# BB_PowerSuppyandMotorDriver_REV1_0.net
KiCad netlist of a schematic drawn in Altium Designer
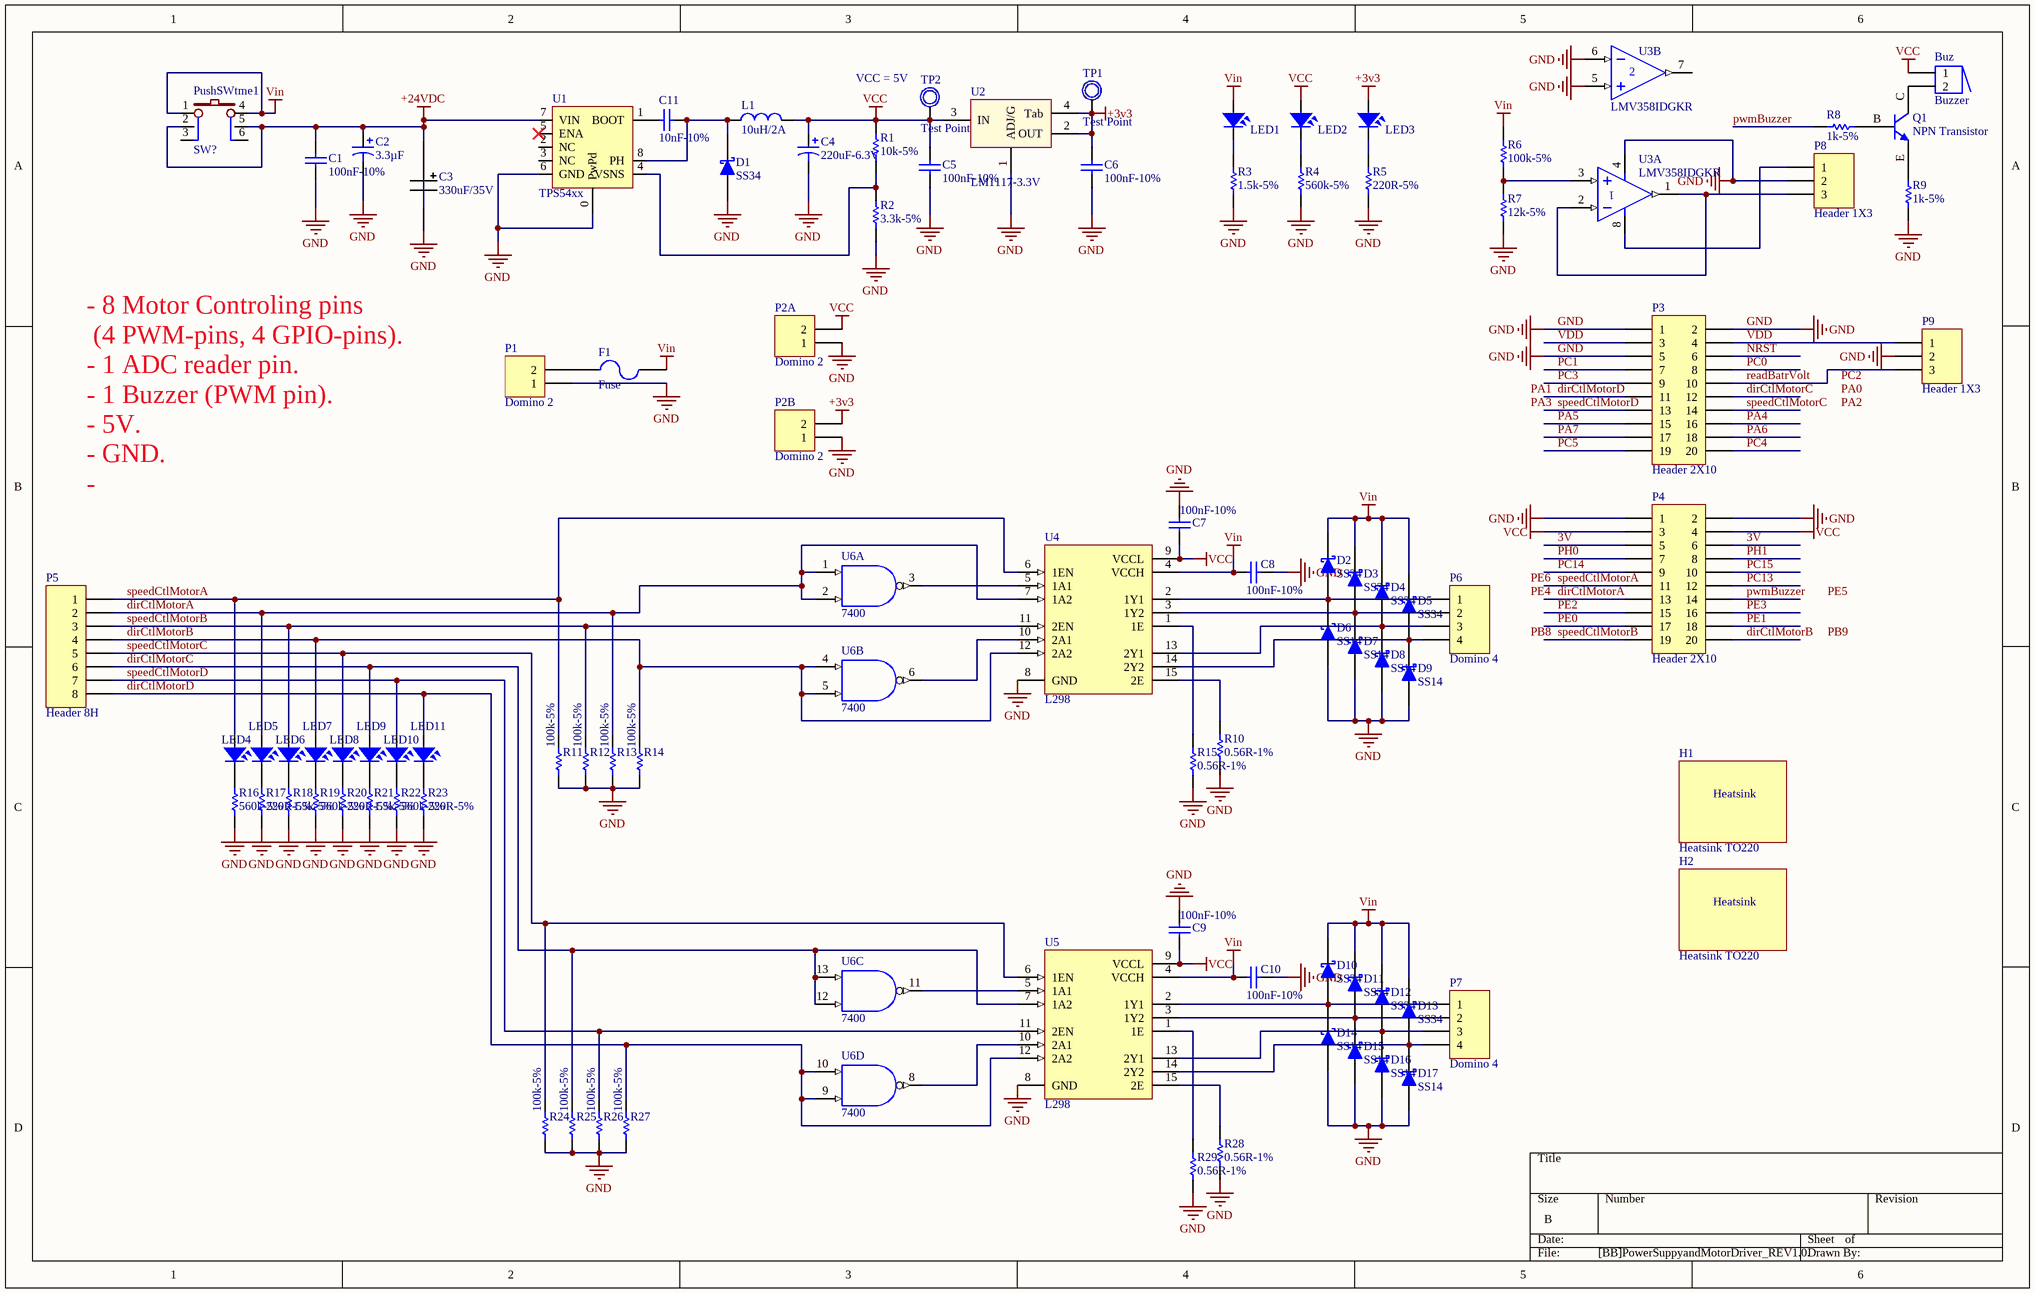
[diagram p0: [BB]PowerSuppyandMotorDriver_REV1.0.SchDoc]

(export (version "E")
  (design (tool "Eeschema 10.0.6"))
  (components
    (comp (ref "Buz")
      (value "Buzzer")
      (footprint "BUZZER SMD")
      (libsource (lib "PIF_Library") (part "Buzzer"))
    )
    (comp (ref "C1")
      (value "100nF-10%")
      (footprint "C0805")
      (description "Non-Polarized Capacitor")
      (fields (field (name "DIGI-KEY PART NUMBER") "311-1140-1-ND") (field (name "MANUFACTURER") "Yageo"))
      (libsource (lib "Capacitor") (part "100nF-50V-C0805"))
    )
    (comp (ref "C2")
      (value "3.3µF")
      (footprint "SM/C_ALU_SA")
      (description "Tantalum Capacitor")
      (fields
        (field (name "MANUFACTURER") "Panasonic Electronic Components")
        (field (name "MANUFACTURER PART NUMBER") "EEE-FC1V3R3R")
      )
      (libsource (lib "Capacitor") (part "4.7uF-25V-Tantalum"))
    )
    (comp (ref "C3")
      (value "330uF/35V")
      (footprint "Size G")
      (description "CAP ALUM 330UF 20% 35V SMD")
      (fields
        (field (name "DIGI-KEY PART NUMBER") "PCE3959CT-ND")
        (field (name "MANUFACTURER") "Panasonic Electronic Components")
      )
      (libsource (lib "Capacitors") (part "C_ALU_330uF_35V"))
    )
    (comp (ref "C4")
      (value "220uF-6.3V")
      (footprint "SM/C_ALU_SD8")
      (description "Tantalum Capacitor")
      (fields
        (field (name "DIGI-KEY PART NUMBER") "478-1713-1-ND")
        (field (name "MANUFACTURER") "AVX Corporation")
      )
      (libsource (lib "Capacitor") (part "220uF-6.3V-Tantalum"))
    )
    (comp (ref "C5")
      (value "100nF-10%")
      (footprint "C0805")
      (description "Non-Polarized Capacitor")
      (fields (field (name "DIGI-KEY PART NUMBER") "311-1140-1-ND") (field (name "MANUFACTURER") "Yageo"))
      (libsource (lib "Capacitor") (part "100nF-50V-C0805"))
    )
    (comp (ref "C6")
      (value "100nF-10%")
      (footprint "C0805")
      (description "Non-Polarized Capacitor")
      (fields (field (name "DIGI-KEY PART NUMBER") "311-1140-1-ND") (field (name "MANUFACTURER") "Yageo"))
      (libsource (lib "Capacitor") (part "100nF-50V-C0805"))
    )
    (comp (ref "C7")
      (value "100nF-10%")
      (footprint "C0805")
      (description "Non-Polarized Capacitor")
      (fields (field (name "DIGI-KEY PART NUMBER") "311-1140-1-ND") (field (name "MANUFACTURER") "Yageo"))
      (libsource (lib "Capacitor") (part "100nF-50V-C0805"))
    )
    (comp (ref "C8")
      (value "100nF-10%")
      (footprint "C0805")
      (description "Non-Polarized Capacitor")
      (fields (field (name "DIGI-KEY PART NUMBER") "311-1140-1-ND") (field (name "MANUFACTURER") "Yageo"))
      (libsource (lib "Capacitor") (part "100nF-50V-C0805"))
    )
    (comp (ref "C9")
      (value "100nF-10%")
      (footprint "C0805")
      (description "Non-Polarized Capacitor")
      (fields (field (name "DIGI-KEY PART NUMBER") "311-1140-1-ND") (field (name "MANUFACTURER") "Yageo"))
      (libsource (lib "Capacitor") (part "100nF-50V-C0805"))
    )
    (comp (ref "C10")
      (value "100nF-10%")
      (footprint "C0805")
      (description "Non-Polarized Capacitor")
      (fields (field (name "DIGI-KEY PART NUMBER") "311-1140-1-ND") (field (name "MANUFACTURER") "Yageo"))
      (libsource (lib "Capacitor") (part "100nF-50V-C0805"))
    )
    (comp (ref "C11")
      (value "10nF-10%")
      (footprint "C0805")
      (description "Non-Polarized Capacitor")
      (fields (field (name "DIGI-KEY PART NUMBER") "311-1136-1-ND") (field (name "MANUFACTURER") "Yageo"))
      (libsource (lib "Capacitor") (part "10nF-50V-C0805"))
    )
    (comp (ref "D1")
      (value "SS34")
      (footprint "DO-214AC (SMA)")
      (description "DIODE SCHOTTKY 40V 1A DO214AC")
      (fields
        (field (name "DIGI-KEY PART NUMBER") "SS14-E3/61TGITR-ND")
        (field (name "MANUFACTURER") "Vishay Semiconductor Diodes Division")
      )
      (libsource (lib "Active Components") (part "Diode_SS14"))
    )
    (comp (ref "D2")
      (value "SS34")
      (footprint "DO-214AC (SMA)")
      (description "DIODE SCHOTTKY 40V 1A DO214AC")
      (fields
        (field (name "DIGI-KEY PART NUMBER") "SS14-E3/61TGITR-ND")
        (field (name "MANUFACTURER") "Vishay Semiconductor Diodes Division")
      )
      (libsource (lib "Active Components") (part "Diode_SS14"))
    )
    (comp (ref "D3")
      (value "SS34")
      (footprint "DO-214AC (SMA)")
      (description "DIODE SCHOTTKY 40V 1A DO214AC")
      (fields
        (field (name "DIGI-KEY PART NUMBER") "SS14-E3/61TGITR-ND")
        (field (name "MANUFACTURER") "Vishay Semiconductor Diodes Division")
      )
      (libsource (lib "Active Components") (part "Diode_SS14"))
    )
    (comp (ref "D4")
      (value "SS34")
      (footprint "DO-214AC (SMA)")
      (description "DIODE SCHOTTKY 40V 1A DO214AC")
      (fields
        (field (name "DIGI-KEY PART NUMBER") "SS14-E3/61TGITR-ND")
        (field (name "MANUFACTURER") "Vishay Semiconductor Diodes Division")
      )
      (libsource (lib "Active Components") (part "Diode_SS14"))
    )
    (comp (ref "D5")
      (value "SS34")
      (footprint "DO-214AC (SMA)")
      (description "DIODE SCHOTTKY 40V 1A DO214AC")
      (fields
        (field (name "DIGI-KEY PART NUMBER") "SS14-E3/61TGITR-ND")
        (field (name "MANUFACTURER") "Vishay Semiconductor Diodes Division")
      )
      (libsource (lib "Active Components") (part "Diode_SS14"))
    )
    (comp (ref "D6")
      (value "SS14")
      (footprint "DO-214AC (SMA)")
      (description "DIODE SCHOTTKY 40V 1A DO214AC")
      (fields
        (field (name "DIGI-KEY PART NUMBER") "SS14-E3/61TGITR-ND")
        (field (name "MANUFACTURER") "Vishay Semiconductor Diodes Division")
      )
      (libsource (lib "Active Components") (part "Diode_SS14"))
    )
    (comp (ref "D7")
      (value "SS14")
      (footprint "DO-214AC (SMA)")
      (description "DIODE SCHOTTKY 40V 1A DO214AC")
      (fields
        (field (name "DIGI-KEY PART NUMBER") "SS14-E3/61TGITR-ND")
        (field (name "MANUFACTURER") "Vishay Semiconductor Diodes Division")
      )
      (libsource (lib "Active Components") (part "Diode_SS14"))
    )
    (comp (ref "D8")
      (value "SS14")
      (footprint "DO-214AC (SMA)")
      (description "DIODE SCHOTTKY 40V 1A DO214AC")
      (fields
        (field (name "DIGI-KEY PART NUMBER") "SS14-E3/61TGITR-ND")
        (field (name "MANUFACTURER") "Vishay Semiconductor Diodes Division")
      )
      (libsource (lib "Active Components") (part "Diode_SS14"))
    )
    (comp (ref "D9")
      (value "SS14")
      (footprint "DO-214AC (SMA)")
      (description "DIODE SCHOTTKY 40V 1A DO214AC")
      (fields
        (field (name "DIGI-KEY PART NUMBER") "SS14-E3/61TGITR-ND")
        (field (name "MANUFACTURER") "Vishay Semiconductor Diodes Division")
      )
      (libsource (lib "Active Components") (part "Diode_SS14"))
    )
    (comp (ref "D10")
      (value "SS34")
      (footprint "DO-214AC (SMA)")
      (description "DIODE SCHOTTKY 40V 1A DO214AC")
      (fields
        (field (name "DIGI-KEY PART NUMBER") "SS14-E3/61TGITR-ND")
        (field (name "MANUFACTURER") "Vishay Semiconductor Diodes Division")
      )
      (libsource (lib "Active Components") (part "Diode_SS14"))
    )
    (comp (ref "D11")
      (value "SS34")
      (footprint "DO-214AC (SMA)")
      (description "DIODE SCHOTTKY 40V 1A DO214AC")
      (fields
        (field (name "DIGI-KEY PART NUMBER") "SS14-E3/61TGITR-ND")
        (field (name "MANUFACTURER") "Vishay Semiconductor Diodes Division")
      )
      (libsource (lib "Active Components") (part "Diode_SS14"))
    )
    (comp (ref "D12")
      (value "SS34")
      (footprint "DO-214AC (SMA)")
      (description "DIODE SCHOTTKY 40V 1A DO214AC")
      (fields
        (field (name "DIGI-KEY PART NUMBER") "SS14-E3/61TGITR-ND")
        (field (name "MANUFACTURER") "Vishay Semiconductor Diodes Division")
      )
      (libsource (lib "Active Components") (part "Diode_SS14"))
    )
    (comp (ref "D13")
      (value "SS34")
      (footprint "DO-214AC (SMA)")
      (description "DIODE SCHOTTKY 40V 1A DO214AC")
      (fields
        (field (name "DIGI-KEY PART NUMBER") "SS14-E3/61TGITR-ND")
        (field (name "MANUFACTURER") "Vishay Semiconductor Diodes Division")
      )
      (libsource (lib "Active Components") (part "Diode_SS14"))
    )
    (comp (ref "D14")
      (value "SS14")
      (footprint "DO-214AC (SMA)")
      (description "DIODE SCHOTTKY 40V 1A DO214AC")
      (fields
        (field (name "DIGI-KEY PART NUMBER") "SS14-E3/61TGITR-ND")
        (field (name "MANUFACTURER") "Vishay Semiconductor Diodes Division")
      )
      (libsource (lib "Active Components") (part "Diode_SS14"))
    )
    (comp (ref "D15")
      (value "SS14")
      (footprint "DO-214AC (SMA)")
      (description "DIODE SCHOTTKY 40V 1A DO214AC")
      (fields
        (field (name "DIGI-KEY PART NUMBER") "SS14-E3/61TGITR-ND")
        (field (name "MANUFACTURER") "Vishay Semiconductor Diodes Division")
      )
      (libsource (lib "Active Components") (part "Diode_SS14"))
    )
    (comp (ref "D16")
      (value "SS14")
      (footprint "DO-214AC (SMA)")
      (description "DIODE SCHOTTKY 40V 1A DO214AC")
      (fields
        (field (name "DIGI-KEY PART NUMBER") "SS14-E3/61TGITR-ND")
        (field (name "MANUFACTURER") "Vishay Semiconductor Diodes Division")
      )
      (libsource (lib "Active Components") (part "Diode_SS14"))
    )
    (comp (ref "D17")
      (value "SS14")
      (footprint "DO-214AC (SMA)")
      (description "DIODE SCHOTTKY 40V 1A DO214AC")
      (fields
        (field (name "DIGI-KEY PART NUMBER") "SS14-E3/61TGITR-ND")
        (field (name "MANUFACTURER") "Vishay Semiconductor Diodes Division")
      )
      (libsource (lib "Active Components") (part "Diode_SS14"))
    )
    (comp (ref "F1")
      (value "Fuse")
      (footprint "FUSE")
      (fields (field (name "PUBLISHER") "Altium Limited"))
      (libsource (lib "Others") (part "Fuse"))
    )
    (comp (ref "H1")
      (value "Heatsink TO220")
      (footprint "Heatsink TO-220")
      (description "Heatsink-231625W Tản nhiệt Nhôm kiểu TO-220 / Multiwatt, 23x16x25mm")
      (libsource (lib "Heatsink") (part "Heatsink TO220"))
    )
    (comp (ref "H2")
      (value "Heatsink TO220")
      (footprint "Heatsink TO-220")
      (description "Heatsink-231625W Tản nhiệt Nhôm kiểu TO-220 / Multiwatt, 23x16x25mm")
      (libsource (lib "Heatsink") (part "Heatsink TO220"))
    )
    (comp (ref "L1")
      (value "10uH/2A")
      (footprint "L6D38")
      (description "10uH/2A ±20% SMD 6.7x6.7x4mm Inductor")
      (libsource (lib "Inductor") (part "L6D38-100M"))
    )
    (comp (ref "LED1")
      (value "LED SMD")
      (footprint "SM-LED-0805-Blue")
      (libsource (lib "syhaunguyen") (part "LED-SMD-0805"))
    )
    (comp (ref "LED2")
      (value "LED SMD")
      (footprint "SM-LED-0805-Blue")
      (libsource (lib "syhaunguyen") (part "LED-SMD-0805"))
    )
    (comp (ref "LED3")
      (value "LED SMD")
      (footprint "SM-LED-0805-Blue")
      (libsource (lib "syhaunguyen") (part "LED-SMD-0805"))
    )
    (comp (ref "LED4")
      (value "LED SMD")
      (footprint "SM-LED-0805-Blue")
      (libsource (lib "syhaunguyen") (part "LED-SMD-0805"))
    )
    (comp (ref "LED5")
      (value "LED SMD")
      (footprint "SM-LED-0805-Blue")
      (libsource (lib "syhaunguyen") (part "LED-SMD-0805"))
    )
    (comp (ref "LED6")
      (value "LED SMD")
      (footprint "SM-LED-0805-Blue")
      (libsource (lib "syhaunguyen") (part "LED-SMD-0805"))
    )
    (comp (ref "LED7")
      (value "LED SMD")
      (footprint "SM-LED-0805-Blue")
      (libsource (lib "syhaunguyen") (part "LED-SMD-0805"))
    )
    (comp (ref "LED8")
      (value "LED SMD")
      (footprint "SM-LED-0805-Blue")
      (libsource (lib "syhaunguyen") (part "LED-SMD-0805"))
    )
    (comp (ref "LED9")
      (value "LED SMD")
      (footprint "SM-LED-0805-Blue")
      (libsource (lib "syhaunguyen") (part "LED-SMD-0805"))
    )
    (comp (ref "LED10")
      (value "LED SMD")
      (footprint "SM-LED-0805-Blue")
      (libsource (lib "syhaunguyen") (part "LED-SMD-0805"))
    )
    (comp (ref "LED11")
      (value "LED SMD")
      (footprint "SM-LED-0805-Blue")
      (libsource (lib "syhaunguyen") (part "LED-SMD-0805"))
    )
    (comp (ref "P1")
      (value "Domino 2")
      (footprint "DOMINO 2- 5mm")
      (description "Domino, 2-Pin")
      (fields (field (name "PUBLISHER") "Altium Limited"))
      (libsource (lib "PIF_Library") (part "Domino 2"))
    )
    (comp (ref "P2A")
      (value "Domino 2")
      (footprint "DOMINO 2- 5mm")
      (description "Domino, 2-Pin")
      (fields (field (name "PUBLISHER") "Altium Limited"))
      (libsource (lib "PIF_Library") (part "Domino 2"))
    )
    (comp (ref "P2B")
      (value "Domino 2")
      (footprint "DOMINO 2- 5mm")
      (description "Domino, 2-Pin")
      (fields (field (name "PUBLISHER") "Altium Limited"))
      (libsource (lib "PIF_Library") (part "Domino 2"))
    )
    (comp (ref "P3")
      (value "Header 2X10")
      (footprint "Header 2X10")
      (description "Header, 10-Pin, Dual row")
      (libsource (lib "Connector") (part "Header 2X10"))
    )
    (comp (ref "P4")
      (value "Header 2X10")
      (footprint "Header 2X10")
      (description "Header, 10-Pin, Dual row")
      (libsource (lib "Connector") (part "Header 2X10"))
    )
    (comp (ref "P5")
      (value "Header 8H")
      (footprint "JP8H")
      (description "Header, 8-Pin, Right Angle")
      (fields (field (name "PUBLISHER") "Altium Limited"))
      (libsource (lib "PIF_Library") (part "Header 8H"))
    )
    (comp (ref "P6")
      (value "Domino 4")
      (footprint "DOMINO 4 -5mm")
      (description "Domino 4-Pin")
      (fields (field (name "PUBLISHER") "Altium Limited"))
      (libsource (lib "PIF_Library") (part "Domino 4"))
    )
    (comp (ref "P7")
      (value "Domino 4")
      (footprint "DOMINO 4 -5mm")
      (description "Domino 4-Pin")
      (fields (field (name "PUBLISHER") "Altium Limited"))
      (libsource (lib "PIF_Library") (part "Domino 4"))
    )
    (comp (ref "P8")
      (value "Header 1X3")
      (footprint "Header 1X3")
      (description "Header, 3-Pin")
      (libsource (lib "Connector") (part "Header 1X3"))
    )
    (comp (ref "P9")
      (value "Header 1X3")
      (footprint "Header 1X3")
      (description "Header, 3-Pin")
      (libsource (lib "Connector") (part "Header 1X3"))
    )
    (comp (ref "PushSWtme1")
      (value "SW?")
      (footprint "PUSH SW")
      (description "Push SW 8x8 mm latching ON/OFF")
      (libsource (lib "Switch, Button & Relay") (part "PushSWtme"))
    )
    (comp (ref "Q1")
      (value "NPN Transistor")
      (footprint "SC-43-BCE")
      (libsource (lib "Transistor") (part "NPN Transistor"))
    )
    (comp (ref "R1")
      (value "10k-5%")
      (footprint "R0805")
      (description "RES 10k OHM 1/8W 5% 0805 SMD")
      (fields (field (name "DIGI-KEY PART NUMBER") "311-10KARTR-ND") (field (name "MANUFACTURER") "Yageo"))
      (libsource (lib "Resistor") (part "10k-5%-R0805"))
    )
    (comp (ref "R2")
      (value "3.3k-5%")
      (footprint "R0805")
      (description "RES 3.3k OHM 1/8W 5% 0805 SMD")
      (fields (field (name "DIGI-KEY PART NUMBER") "311-3.3KARTR-ND") (field (name "MANUFACTURER") "Yageo"))
      (libsource (lib "Resistor") (part "3.3k-5%-R0805"))
    )
    (comp (ref "R3")
      (value "1.5k-5%")
      (footprint "R0805")
      (description "RES 1.5k OHM 1/8W 5% 0805 SMD")
      (fields (field (name "DIGI-KEY PART NUMBER") "311-1.5KARTR-ND") (field (name "MANUFACTURER") "Yageo"))
      (libsource (lib "Resistor") (part "1.5k-5%-R0805"))
    )
    (comp (ref "R4")
      (value "560k-5%")
      (footprint "R0805")
      (description "RES 560k OHM 1/10W 5% 0603 SMD")
      (fields (field (name "DIGI-KEY PART NUMBER") "311-560KGRTR-ND") (field (name "MANUFACTURER") "Yageo"))
      (libsource (lib "Resistor") (part "560k-5%-R0603"))
    )
    (comp (ref "R5")
      (value "220R-5%")
      (footprint "R0805")
      (description "RES 220 OHM 1/8W 5% 0805 SMD")
      (fields (field (name "DIGI-KEY PART NUMBER") "311-220ARTR-ND") (field (name "MANUFACTURER") "Yageo"))
      (libsource (lib "Resistor") (part "220R-5%-R0805"))
    )
    (comp (ref "R6")
      (value "100k-5%")
      (footprint "R0805")
      (description "RES 100k OHM 1/8W 5% 0805 SMD")
      (fields (field (name "DIGI-KEY PART NUMBER") "311-100KARTR-ND") (field (name "MANUFACTURER") "Yageo"))
      (libsource (lib "Resistor") (part "100k-5%-R0805"))
    )
    (comp (ref "R7")
      (value "12k-5%")
      (footprint "R0805")
      (description "RES 12k OHM 1/8W 5% 0805 SMD")
      (fields (field (name "DIGI-KEY PART NUMBER") "311-12KARTR-ND") (field (name "MANUFACTURER") "Yageo"))
      (libsource (lib "Resistor") (part "12k-5%-R0805"))
    )
    (comp (ref "R8")
      (value "1k-5%")
      (footprint "R0805")
      (description "RES 1k OHM 1/8W 5% 0805 SMD")
      (fields (field (name "DIGI-KEY PART NUMBER") "311-1.0KARTR-ND") (field (name "MANUFACTURER") "Yageo"))
      (libsource (lib "Resistor") (part "1k-5%-R0805"))
    )
    (comp (ref "R9")
      (value "1k-5%")
      (footprint "R0805")
      (description "RES 1k OHM 1/8W 5% 0805 SMD")
      (fields (field (name "DIGI-KEY PART NUMBER") "311-1.0KARTR-ND") (field (name "MANUFACTURER") "Yageo"))
      (libsource (lib "Resistor") (part "1k-5%-R0805"))
    )
    (comp (ref "R10")
      (value "0.56R-1%")
      (footprint "R0805")
      (description "RES 0.56 OHM 1/10W 1% 0603 SMD")
      (fields (field (name "DIGI-KEY PART NUMBER") "311-.56QTR-ND") (field (name "MANUFACTURER") "Yageo"))
      (libsource (lib "Resistor") (part "0.56R-1%-R0603"))
    )
    (comp (ref "R11")
      (value "100k-5%")
      (footprint "R0805")
      (description "RES 100k OHM 1/8W 5% 0805 SMD")
      (fields (field (name "DIGI-KEY PART NUMBER") "311-100KARTR-ND") (field (name "MANUFACTURER") "Yageo"))
      (libsource (lib "Resistor") (part "100k-5%-R0805"))
    )
    (comp (ref "R12")
      (value "100k-5%")
      (footprint "R0805")
      (description "RES 100k OHM 1/8W 5% 0805 SMD")
      (fields (field (name "DIGI-KEY PART NUMBER") "311-100KARTR-ND") (field (name "MANUFACTURER") "Yageo"))
      (libsource (lib "Resistor") (part "100k-5%-R0805"))
    )
    (comp (ref "R13")
      (value "100k-5%")
      (footprint "R0805")
      (description "RES 100k OHM 1/8W 5% 0805 SMD")
      (fields (field (name "DIGI-KEY PART NUMBER") "311-100KARTR-ND") (field (name "MANUFACTURER") "Yageo"))
      (libsource (lib "Resistor") (part "100k-5%-R0805"))
    )
    (comp (ref "R14")
      (value "100k-5%")
      (footprint "R0805")
      (description "RES 100k OHM 1/8W 5% 0805 SMD")
      (fields (field (name "DIGI-KEY PART NUMBER") "311-100KARTR-ND") (field (name "MANUFACTURER") "Yageo"))
      (libsource (lib "Resistor") (part "100k-5%-R0805"))
    )
    (comp (ref "R15")
      (value "0.56R-1%")
      (footprint "R0805")
      (description "RES 0.56 OHM 1/10W 1% 0603 SMD")
      (fields (field (name "DIGI-KEY PART NUMBER") "311-.56QTR-ND") (field (name "MANUFACTURER") "Yageo"))
      (libsource (lib "Resistor") (part "0.56R-1%-R0603"))
    )
    (comp (ref "R16")
      (value "560k-5%")
      (footprint "R0805")
      (description "RES 560k OHM 1/10W 5% 0603 SMD")
      (fields (field (name "DIGI-KEY PART NUMBER") "311-560KGRTR-ND") (field (name "MANUFACTURER") "Yageo"))
      (libsource (lib "Resistor") (part "560k-5%-R0603"))
    )
    (comp (ref "R17")
      (value "220R-5%")
      (footprint "R0805")
      (description "RES 220 OHM 1/8W 5% 0805 SMD")
      (fields (field (name "DIGI-KEY PART NUMBER") "311-220ARTR-ND") (field (name "MANUFACTURER") "Yageo"))
      (libsource (lib "Resistor") (part "220R-5%-R0805"))
    )
    (comp (ref "R18")
      (value "1.5k-5%")
      (footprint "R0805")
      (description "RES 1.5k OHM 1/8W 5% 0805 SMD")
      (fields (field (name "DIGI-KEY PART NUMBER") "311-1.5KARTR-ND") (field (name "MANUFACTURER") "Yageo"))
      (libsource (lib "Resistor") (part "1.5k-5%-R0805"))
    )
    (comp (ref "R19")
      (value "560k-5%")
      (footprint "R0805")
      (description "RES 560k OHM 1/10W 5% 0603 SMD")
      (fields (field (name "DIGI-KEY PART NUMBER") "311-560KGRTR-ND") (field (name "MANUFACTURER") "Yageo"))
      (libsource (lib "Resistor") (part "560k-5%-R0603"))
    )
    (comp (ref "R20")
      (value "220R-5%")
      (footprint "R0805")
      (description "RES 220 OHM 1/8W 5% 0805 SMD")
      (fields (field (name "DIGI-KEY PART NUMBER") "311-220ARTR-ND") (field (name "MANUFACTURER") "Yageo"))
      (libsource (lib "Resistor") (part "220R-5%-R0805"))
    )
    (comp (ref "R21")
      (value "1.5k-5%")
      (footprint "R0805")
      (description "RES 1.5k OHM 1/8W 5% 0805 SMD")
      (fields (field (name "DIGI-KEY PART NUMBER") "311-1.5KARTR-ND") (field (name "MANUFACTURER") "Yageo"))
      (libsource (lib "Resistor") (part "1.5k-5%-R0805"))
    )
    (comp (ref "R22")
      (value "560k-5%")
      (footprint "R0805")
      (description "RES 560k OHM 1/10W 5% 0603 SMD")
      (fields (field (name "DIGI-KEY PART NUMBER") "311-560KGRTR-ND") (field (name "MANUFACTURER") "Yageo"))
      (libsource (lib "Resistor") (part "560k-5%-R0603"))
    )
    (comp (ref "R23")
      (value "220R-5%")
      (footprint "R0805")
      (description "RES 220 OHM 1/8W 5% 0805 SMD")
      (fields (field (name "DIGI-KEY PART NUMBER") "311-220ARTR-ND") (field (name "MANUFACTURER") "Yageo"))
      (libsource (lib "Resistor") (part "220R-5%-R0805"))
    )
    (comp (ref "R24")
      (value "100k-5%")
      (footprint "R0805")
      (description "RES 100k OHM 1/8W 5% 0805 SMD")
      (fields (field (name "DIGI-KEY PART NUMBER") "311-100KARTR-ND") (field (name "MANUFACTURER") "Yageo"))
      (libsource (lib "Resistor") (part "100k-5%-R0805"))
    )
    (comp (ref "R25")
      (value "100k-5%")
      (footprint "R0805")
      (description "RES 100k OHM 1/8W 5% 0805 SMD")
      (fields (field (name "DIGI-KEY PART NUMBER") "311-100KARTR-ND") (field (name "MANUFACTURER") "Yageo"))
      (libsource (lib "Resistor") (part "100k-5%-R0805"))
    )
    (comp (ref "R26")
      (value "100k-5%")
      (footprint "R0805")
      (description "RES 100k OHM 1/8W 5% 0805 SMD")
      (fields (field (name "DIGI-KEY PART NUMBER") "311-100KARTR-ND") (field (name "MANUFACTURER") "Yageo"))
      (libsource (lib "Resistor") (part "100k-5%-R0805"))
    )
    (comp (ref "R27")
      (value "100k-5%")
      (footprint "R0805")
      (description "RES 100k OHM 1/8W 5% 0805 SMD")
      (fields (field (name "DIGI-KEY PART NUMBER") "311-100KARTR-ND") (field (name "MANUFACTURER") "Yageo"))
      (libsource (lib "Resistor") (part "100k-5%-R0805"))
    )
    (comp (ref "R28")
      (value "0.56R-1%")
      (footprint "R0805")
      (description "RES 0.56 OHM 1/10W 1% 0603 SMD")
      (fields (field (name "DIGI-KEY PART NUMBER") "311-.56QTR-ND") (field (name "MANUFACTURER") "Yageo"))
      (libsource (lib "Resistor") (part "0.56R-1%-R0603"))
    )
    (comp (ref "R29")
      (value "0.56R-1%")
      (footprint "R0805")
      (description "RES 0.56 OHM 1/10W 1% 0603 SMD")
      (fields (field (name "DIGI-KEY PART NUMBER") "311-.56QTR-ND") (field (name "MANUFACTURER") "Yageo"))
      (libsource (lib "Resistor") (part "0.56R-1%-R0603"))
    )
    (comp (ref "TP1")
      (value "Test Point")
      (footprint "Hole 1.5mm")
      (libsource (lib "Connector") (part "Test Point"))
    )
    (comp (ref "TP2")
      (value "Test Point")
      (footprint "Hole 1.5mm")
      (libsource (lib "Connector") (part "Test Point"))
    )
    (comp (ref "U1")
      (value "TPS54xx")
      (footprint "SOIC-8 POWERPAD")
      (description "IC REG BUCK ADJ 1A 8SOIC")
      (fields
        (field (name "DIGI-KEY PART NUMBER") "296-26982-2-ND")
        (field (name "MANUFACTURER") "Texas Instruments")
      )
      (libsource (lib "power_ic") (part "TPS54xx"))
    )
    (comp (ref "U2")
      (value "LM1117-3.3V")
      (footprint "SOT223-4N")
      (description "800mA Low-Dropout Linear Regulator")
      (fields
        (field (name "DIGI-KEY PART NUMBER") "LM1117MPX-3.3/NOPBTR-ND")
        (field (name "MANUFACTURER") "Texas Instruments")
      )
      (libsource (lib "IC") (part "LM1117-3.3V"))
    )
    (comp (ref "U3")
      (value "LMV358IDGKR")
      (footprint "MSOP-8")
      (fields (field (name "MANUFACTURER") "Texas Instruments"))
      (libsource (lib "Opamp-SMD") (part "LMV358IDGKR"))
    )
    (comp (ref "U4")
      (value "L298")
      (footprint "DIP15SL2")
      (description "Dual Full-H Driver")
      (fields (field (name "PUBLISHER") "Altium Limited"))
      (libsource (lib "IC") (part "L298"))
    )
    (comp (ref "U5")
      (value "L298")
      (footprint "DIP15SL2")
      (description "Dual Full-H Driver")
      (fields (field (name "PUBLISHER") "Altium Limited"))
      (libsource (lib "IC") (part "L298"))
    )
    (comp (ref "U6")
      (value "7400")
      (footprint "SO14-150mil")
      (description "Quad 2-Input NAND Gate")
      (libsource (lib "IC") (part "7400"))
    )
  )
  (nets
    (net (code "1") (name "+3v3") (class "Default")
      (node (ref "C6") (pin "2") (pinfunction "2_2") (pintype "passive"))
      (node (ref "LED3") (pin "1") (pinfunction "1_1") (pintype "passive"))
      (node (ref "P2B") (pin "2") (pinfunction "2_2") (pintype "passive"))
      (node (ref "TP1") (pin "0") (pinfunction "0_0") (pintype "passive"))
      (node (ref "U2") (pin "2") (pinfunction "OUT_2") (pintype "passive"))
      (node (ref "U2") (pin "4") (pinfunction "Tab_4") (pintype "passive"))
    )
    (net (code "2") (name "+24VDC") (class "Default")
      (node (ref "C1") (pin "2") (pinfunction "2_2") (pintype "passive"))
      (node (ref "C2") (pin "1") (pinfunction "1_1") (pintype "passive"))
      (node (ref "C3") (pin "1") (pintype "passive"))
      (node (ref "PushSWtme1") (pin "2") (pinfunction "2_2") (pintype "passive"))
      (node (ref "PushSWtme1") (pin "5") (pinfunction "5_5") (pintype "passive"))
      (node (ref "U1") (pin "7") (pinfunction "VIN_7") (pintype "passive"))
    )
    (net (code "3") (name "/3V") (class "Default")
      (node (ref "P4") (pin "5") (pinfunction "5_5") (pintype "passive"))
      (node (ref "P4") (pin "6") (pinfunction "6_6") (pintype "passive"))
    )
    (net (code "4") (name "/NRST") (class "Default")
      (node (ref "P3") (pin "6") (pinfunction "6_6") (pintype "passive"))
    )
    (net (code "9") (name "/PA4") (class "Default")
      (node (ref "P3") (pin "16") (pinfunction "16_16") (pintype "passive"))
    )
    (net (code "10") (name "/PA5") (class "Default")
      (node (ref "P3") (pin "15") (pinfunction "15_15") (pintype "passive"))
    )
    (net (code "11") (name "/PA6") (class "Default")
      (node (ref "P3") (pin "18") (pinfunction "18_18") (pintype "passive"))
    )
    (net (code "12") (name "/PA7") (class "Default")
      (node (ref "P3") (pin "17") (pinfunction "17_17") (pintype "passive"))
    )
    (net (code "15") (name "/PC0") (class "Default")
      (node (ref "P3") (pin "8") (pinfunction "8_8") (pintype "passive"))
    )
    (net (code "16") (name "/PC1") (class "Default")
      (node (ref "P3") (pin "7") (pinfunction "7_7") (pintype "passive"))
    )
    (net (code "18") (name "/PC3") (class "Default")
      (node (ref "P3") (pin "9") (pinfunction "9_9") (pintype "passive"))
    )
    (net (code "19") (name "/PC4") (class "Default")
      (node (ref "P3") (pin "20") (pinfunction "20_20") (pintype "passive"))
    )
    (net (code "20") (name "/PC5") (class "Default")
      (node (ref "P3") (pin "19") (pinfunction "19_19") (pintype "passive"))
    )
    (net (code "21") (name "/PC13") (class "Default")
      (node (ref "P4") (pin "12") (pinfunction "12_12") (pintype "passive"))
    )
    (net (code "22") (name "/PC14") (class "Default")
      (node (ref "P4") (pin "9") (pinfunction "9_9") (pintype "passive"))
    )
    (net (code "23") (name "/PC15") (class "Default")
      (node (ref "P4") (pin "10") (pinfunction "10_10") (pintype "passive"))
    )
    (net (code "24") (name "/PE0") (class "Default")
      (node (ref "P4") (pin "17") (pinfunction "17_17") (pintype "passive"))
    )
    (net (code "25") (name "/PE1") (class "Default")
      (node (ref "P4") (pin "18") (pinfunction "18_18") (pintype "passive"))
    )
    (net (code "26") (name "/PE2") (class "Default")
      (node (ref "P4") (pin "15") (pinfunction "15_15") (pintype "passive"))
    )
    (net (code "27") (name "/PE3") (class "Default")
      (node (ref "P4") (pin "16") (pinfunction "16_16") (pintype "passive"))
    )
    (net (code "31") (name "/PH0") (class "Default")
      (node (ref "P4") (pin "7") (pinfunction "7_7") (pintype "passive"))
    )
    (net (code "32") (name "/PH1") (class "Default")
      (node (ref "P4") (pin "8") (pinfunction "8_8") (pintype "passive"))
    )
    (net (code "33") (name "/VDD") (class "Default")
      (node (ref "P3") (pin "3") (pinfunction "3_3") (pintype "passive"))
      (node (ref "P3") (pin "4") (pinfunction "4_4") (pintype "passive"))
      (node (ref "P9") (pin "1") (pinfunction "1_1") (pintype "passive"))
    )
    (net (code "34") (name "/dirCtlMotorA") (class "Default")
      (node (ref "LED5") (pin "1") (pinfunction "1_1") (pintype "passive"))
      (node (ref "P4") (pin "13") (pinfunction "13_13") (pintype "passive"))
      (node (ref "P5") (pin "2") (pinfunction "2_2") (pintype "passive"))
      (node (ref "R13") (pin "2") (pinfunction "2_2") (pintype "passive"))
      (node (ref "U4") (pin "7") (pinfunction "1A2_7") (pintype "input"))
      (node (ref "U6") (pin "1") (pinfunction "A_1") (pintype "input"))
      (node (ref "U6") (pin "2") (pinfunction "B_2") (pintype "input"))
    )
    (net (code "35") (name "/dirCtlMotorB") (class "Default")
      (node (ref "LED7") (pin "1") (pinfunction "1_1") (pintype "passive"))
      (node (ref "P4") (pin "20") (pinfunction "20_20") (pintype "passive"))
      (node (ref "P5") (pin "4") (pinfunction "4_4") (pintype "passive"))
      (node (ref "R14") (pin "2") (pinfunction "2_2") (pintype "passive"))
      (node (ref "U4") (pin "12") (pinfunction "2A2_12") (pintype "input"))
      (node (ref "U6") (pin "4") (pinfunction "A_4") (pintype "input"))
      (node (ref "U6") (pin "5") (pinfunction "B_5") (pintype "input"))
    )
    (net (code "36") (name "/dirCtlMotorC") (class "Default")
      (node (ref "LED9") (pin "1") (pinfunction "1_1") (pintype "passive"))
      (node (ref "P3") (pin "12") (pinfunction "12_12") (pintype "passive"))
      (node (ref "P5") (pin "6") (pinfunction "6_6") (pintype "passive"))
      (node (ref "R25") (pin "2") (pinfunction "2_2") (pintype "passive"))
      (node (ref "U5") (pin "7") (pinfunction "1A2_7") (pintype "input"))
      (node (ref "U6") (pin "12") (pinfunction "B_12") (pintype "input"))
      (node (ref "U6") (pin "13") (pinfunction "A_13") (pintype "input"))
    )
    (net (code "37") (name "/dirCtlMotorD") (class "Default")
      (node (ref "LED11") (pin "1") (pinfunction "1_1") (pintype "passive"))
      (node (ref "P3") (pin "11") (pinfunction "11_11") (pintype "passive"))
      (node (ref "P5") (pin "8") (pinfunction "8_8") (pintype "passive"))
      (node (ref "R27") (pin "2") (pinfunction "2_2") (pintype "passive"))
      (node (ref "U5") (pin "12") (pinfunction "2A2_12") (pintype "input"))
      (node (ref "U6") (pin "10") (pinfunction "A_10") (pintype "input"))
      (node (ref "U6") (pin "9") (pinfunction "B_9") (pintype "input"))
    )
    (net (code "38") (name "/pwmBuzzer") (class "Default")
      (node (ref "P4") (pin "14") (pinfunction "14_14") (pintype "passive"))
      (node (ref "R8") (pin "1") (pinfunction "1_1") (pintype "passive"))
    )
    (net (code "39") (name "/readBatrVolt") (class "Default")
      (node (ref "P3") (pin "10") (pinfunction "10_10") (pintype "passive"))
      (node (ref "P9") (pin "3") (pinfunction "3_3") (pintype "passive"))
    )
    (net (code "40") (name "/speedCtlMotorA") (class "Default")
      (node (ref "LED4") (pin "1") (pinfunction "1_1") (pintype "passive"))
      (node (ref "P4") (pin "11") (pinfunction "11_11") (pintype "passive"))
      (node (ref "P5") (pin "1") (pinfunction "1_1") (pintype "passive"))
      (node (ref "R11") (pin "2") (pinfunction "2_2") (pintype "passive"))
      (node (ref "U4") (pin "6") (pinfunction "1EN_6") (pintype "input"))
    )
    (net (code "41") (name "/speedCtlMotorB") (class "Default")
      (node (ref "LED6") (pin "1") (pinfunction "1_1") (pintype "passive"))
      (node (ref "P4") (pin "19") (pinfunction "19_19") (pintype "passive"))
      (node (ref "P5") (pin "3") (pinfunction "3_3") (pintype "passive"))
      (node (ref "R12") (pin "2") (pinfunction "2_2") (pintype "passive"))
      (node (ref "U4") (pin "11") (pinfunction "2EN_11") (pintype "input"))
    )
    (net (code "42") (name "/speedCtlMotorC") (class "Default")
      (node (ref "LED8") (pin "1") (pinfunction "1_1") (pintype "passive"))
      (node (ref "P3") (pin "14") (pinfunction "14_14") (pintype "passive"))
      (node (ref "P5") (pin "5") (pinfunction "5_5") (pintype "passive"))
      (node (ref "R24") (pin "2") (pinfunction "2_2") (pintype "passive"))
      (node (ref "U5") (pin "6") (pinfunction "1EN_6") (pintype "input"))
    )
    (net (code "43") (name "/speedCtlMotorD") (class "Default")
      (node (ref "LED10") (pin "1") (pinfunction "1_1") (pintype "passive"))
      (node (ref "P3") (pin "13") (pinfunction "13_13") (pintype "passive"))
      (node (ref "P5") (pin "7") (pinfunction "7_7") (pintype "passive"))
      (node (ref "R26") (pin "2") (pinfunction "2_2") (pintype "passive"))
      (node (ref "U5") (pin "11") (pinfunction "2EN_11") (pintype "input"))
    )
    (net (code "44") (name "GND") (class "Default")
      (node (ref "C1") (pin "1") (pinfunction "1_1") (pintype "passive"))
      (node (ref "C10") (pin "1") (pinfunction "1_1") (pintype "passive"))
      (node (ref "C2") (pin "2") (pinfunction "2_2") (pintype "passive"))
      (node (ref "C3") (pin "2") (pintype "passive"))
      (node (ref "C4") (pin "2") (pinfunction "2_2") (pintype "passive"))
      (node (ref "C5") (pin "1") (pinfunction "1_1") (pintype "passive"))
      (node (ref "C6") (pin "1") (pinfunction "1_1") (pintype "passive"))
      (node (ref "C7") (pin "2") (pinfunction "2_2") (pintype "passive"))
      (node (ref "C8") (pin "1") (pinfunction "1_1") (pintype "passive"))
      (node (ref "C9") (pin "2") (pinfunction "2_2") (pintype "passive"))
      (node (ref "D1") (pin "1") (pinfunction "A_1") (pintype "passive"))
      (node (ref "D14") (pin "1") (pinfunction "A_1") (pintype "passive"))
      (node (ref "D15") (pin "1") (pinfunction "A_1") (pintype "passive"))
      (node (ref "D16") (pin "1") (pinfunction "A_1") (pintype "passive"))
      (node (ref "D17") (pin "1") (pinfunction "A_1") (pintype "passive"))
      (node (ref "D6") (pin "1") (pinfunction "A_1") (pintype "passive"))
      (node (ref "D7") (pin "1") (pinfunction "A_1") (pintype "passive"))
      (node (ref "D8") (pin "1") (pinfunction "A_1") (pintype "passive"))
      (node (ref "D9") (pin "1") (pinfunction "A_1") (pintype "passive"))
      (node (ref "P1") (pin "1") (pinfunction "1_1") (pintype "passive"))
      (node (ref "P2A") (pin "1") (pinfunction "1_1") (pintype "passive"))
      (node (ref "P2B") (pin "1") (pinfunction "1_1") (pintype "passive"))
      (node (ref "P3") (pin "1") (pinfunction "1_1") (pintype "passive"))
      (node (ref "P3") (pin "2") (pinfunction "2_2") (pintype "passive"))
      (node (ref "P3") (pin "5") (pinfunction "5_5") (pintype "passive"))
      (node (ref "P4") (pin "1") (pinfunction "1_1") (pintype "passive"))
      (node (ref "P4") (pin "2") (pinfunction "2_2") (pintype "passive"))
      (node (ref "P8") (pin "2") (pinfunction "2_2") (pintype "passive"))
      (node (ref "P9") (pin "2") (pinfunction "2_2") (pintype "passive"))
      (node (ref "R10") (pin "1") (pinfunction "1_1") (pintype "passive"))
      (node (ref "R11") (pin "1") (pinfunction "1_1") (pintype "passive"))
      (node (ref "R12") (pin "1") (pinfunction "1_1") (pintype "passive"))
      (node (ref "R13") (pin "1") (pinfunction "1_1") (pintype "passive"))
      (node (ref "R14") (pin "1") (pinfunction "1_1") (pintype "passive"))
      (node (ref "R15") (pin "1") (pinfunction "1_1") (pintype "passive"))
      (node (ref "R16") (pin "1") (pinfunction "1_1") (pintype "passive"))
      (node (ref "R17") (pin "1") (pinfunction "1_1") (pintype "passive"))
      (node (ref "R18") (pin "1") (pinfunction "1_1") (pintype "passive"))
      (node (ref "R19") (pin "1") (pinfunction "1_1") (pintype "passive"))
      (node (ref "R2") (pin "1") (pinfunction "1_1") (pintype "passive"))
      (node (ref "R20") (pin "1") (pinfunction "1_1") (pintype "passive"))
      (node (ref "R21") (pin "1") (pinfunction "1_1") (pintype "passive"))
      (node (ref "R22") (pin "1") (pinfunction "1_1") (pintype "passive"))
      (node (ref "R23") (pin "1") (pinfunction "1_1") (pintype "passive"))
      (node (ref "R24") (pin "1") (pinfunction "1_1") (pintype "passive"))
      (node (ref "R25") (pin "1") (pinfunction "1_1") (pintype "passive"))
      (node (ref "R26") (pin "1") (pinfunction "1_1") (pintype "passive"))
      (node (ref "R27") (pin "1") (pinfunction "1_1") (pintype "passive"))
      (node (ref "R28") (pin "1") (pinfunction "1_1") (pintype "passive"))
      (node (ref "R29") (pin "1") (pinfunction "1_1") (pintype "passive"))
      (node (ref "R3") (pin "1") (pinfunction "1_1") (pintype "passive"))
      (node (ref "R4") (pin "1") (pinfunction "1_1") (pintype "passive"))
      (node (ref "R5") (pin "1") (pinfunction "1_1") (pintype "passive"))
      (node (ref "R7") (pin "1") (pinfunction "1_1") (pintype "passive"))
      (node (ref "R9") (pin "1") (pinfunction "1_1") (pintype "passive"))
      (node (ref "U1") (pin "0") (pinfunction "PwPd_0") (pintype "passive"))
      (node (ref "U1") (pin "6") (pinfunction "GND_6") (pintype "passive"))
      (node (ref "U2") (pin "1") (pinfunction "ADJ/G_1") (pintype "passive"))
      (node (ref "U3") (pin "4") (pinfunction "V-_4") (pintype "power_in"))
      (node (ref "U3") (pin "5") (pinfunction "IN+_5") (pintype "input"))
      (node (ref "U3") (pin "6") (pinfunction "IN-_6") (pintype "input"))
      (node (ref "U4") (pin "8") (pinfunction "GND_8") (pintype "power_in"))
      (node (ref "U5") (pin "8") (pinfunction "GND_8") (pintype "power_in"))
      (node (ref "U6") (pin "7") (pinfunction "GND_7") (pintype "power_in"))
    )
    (net (code "45") (name "Net-(Buz-Pad2)") (class "Default")
      (node (ref "Buz") (pin "2") (pinfunction "2_2") (pintype "passive"))
      (node (ref "Q1") (pin "C") (pinfunction "C_C") (pintype "passive"))
    )
    (net (code "46") (name "Net-(D1-K)") (class "Default")
      (node (ref "C11") (pin "2") (pinfunction "2_2") (pintype "passive"))
      (node (ref "D1") (pin "2") (pinfunction "K_2") (pintype "passive"))
      (node (ref "L1") (pin "1") (pinfunction "1_1") (pintype "passive"))
      (node (ref "U1") (pin "8") (pinfunction "PH_8") (pintype "passive"))
    )
    (net (code "47") (name "Net-(D2-A)") (class "Default")
      (node (ref "D2") (pin "1") (pinfunction "A_1") (pintype "passive"))
      (node (ref "D6") (pin "2") (pinfunction "K_2") (pintype "passive"))
      (node (ref "P6") (pin "1") (pinfunction "1_1") (pintype "passive"))
      (node (ref "U4") (pin "2") (pinfunction "1Y1_2") (pintype "tri_state"))
    )
    (net (code "48") (name "Net-(D3-A)") (class "Default")
      (node (ref "D3") (pin "1") (pinfunction "A_1") (pintype "passive"))
      (node (ref "D7") (pin "2") (pinfunction "K_2") (pintype "passive"))
      (node (ref "P6") (pin "2") (pinfunction "2_2") (pintype "passive"))
      (node (ref "U4") (pin "3") (pinfunction "1Y2_3") (pintype "tri_state"))
    )
    (net (code "49") (name "Net-(D4-A)") (class "Default")
      (node (ref "D4") (pin "1") (pinfunction "A_1") (pintype "passive"))
      (node (ref "D8") (pin "2") (pinfunction "K_2") (pintype "passive"))
      (node (ref "P6") (pin "3") (pinfunction "3_3") (pintype "passive"))
      (node (ref "U4") (pin "13") (pinfunction "2Y1_13") (pintype "tri_state"))
    )
    (net (code "50") (name "Net-(D5-A)") (class "Default")
      (node (ref "D5") (pin "1") (pinfunction "A_1") (pintype "passive"))
      (node (ref "D9") (pin "2") (pinfunction "K_2") (pintype "passive"))
      (node (ref "P6") (pin "4") (pinfunction "4_4") (pintype "passive"))
      (node (ref "U4") (pin "14") (pinfunction "2Y2_14") (pintype "tri_state"))
    )
    (net (code "51") (name "Net-(D10-A)") (class "Default")
      (node (ref "D10") (pin "1") (pinfunction "A_1") (pintype "passive"))
      (node (ref "D14") (pin "2") (pinfunction "K_2") (pintype "passive"))
      (node (ref "P7") (pin "1") (pinfunction "1_1") (pintype "passive"))
      (node (ref "U5") (pin "2") (pinfunction "1Y1_2") (pintype "tri_state"))
    )
    (net (code "52") (name "Net-(D11-A)") (class "Default")
      (node (ref "D11") (pin "1") (pinfunction "A_1") (pintype "passive"))
      (node (ref "D15") (pin "2") (pinfunction "K_2") (pintype "passive"))
      (node (ref "P7") (pin "2") (pinfunction "2_2") (pintype "passive"))
      (node (ref "U5") (pin "3") (pinfunction "1Y2_3") (pintype "tri_state"))
    )
    (net (code "53") (name "Net-(D12-A)") (class "Default")
      (node (ref "D12") (pin "1") (pinfunction "A_1") (pintype "passive"))
      (node (ref "D16") (pin "2") (pinfunction "K_2") (pintype "passive"))
      (node (ref "P7") (pin "3") (pinfunction "3_3") (pintype "passive"))
      (node (ref "U5") (pin "13") (pinfunction "2Y1_13") (pintype "tri_state"))
    )
    (net (code "54") (name "Net-(D13-A)") (class "Default")
      (node (ref "D13") (pin "1") (pinfunction "A_1") (pintype "passive"))
      (node (ref "D17") (pin "2") (pinfunction "K_2") (pintype "passive"))
      (node (ref "P7") (pin "4") (pinfunction "4_4") (pintype "passive"))
      (node (ref "U5") (pin "14") (pinfunction "2Y2_14") (pintype "tri_state"))
    )
    (net (code "55") (name "Net-(F1-Pad1)") (class "Default")
      (node (ref "F1") (pin "1") (pinfunction "1_1") (pintype "passive"))
      (node (ref "P1") (pin "2") (pinfunction "2_2") (pintype "passive"))
    )
    (net (code "56") (name "Net-(LED1-Pad2)") (class "Default")
      (node (ref "LED1") (pin "2") (pinfunction "2_2") (pintype "passive"))
      (node (ref "R3") (pin "2") (pinfunction "2_2") (pintype "passive"))
    )
    (net (code "57") (name "Net-(LED2-Pad2)") (class "Default")
      (node (ref "LED2") (pin "2") (pinfunction "2_2") (pintype "passive"))
      (node (ref "R4") (pin "2") (pinfunction "2_2") (pintype "passive"))
    )
    (net (code "58") (name "Net-(LED3-Pad2)") (class "Default")
      (node (ref "LED3") (pin "2") (pinfunction "2_2") (pintype "passive"))
      (node (ref "R5") (pin "2") (pinfunction "2_2") (pintype "passive"))
    )
    (net (code "59") (name "Net-(LED4-Pad2)") (class "Default")
      (node (ref "LED4") (pin "2") (pinfunction "2_2") (pintype "passive"))
      (node (ref "R16") (pin "2") (pinfunction "2_2") (pintype "passive"))
    )
    (net (code "60") (name "Net-(LED5-Pad2)") (class "Default")
      (node (ref "LED5") (pin "2") (pinfunction "2_2") (pintype "passive"))
      (node (ref "R17") (pin "2") (pinfunction "2_2") (pintype "passive"))
    )
    (net (code "61") (name "Net-(LED6-Pad2)") (class "Default")
      (node (ref "LED6") (pin "2") (pinfunction "2_2") (pintype "passive"))
      (node (ref "R18") (pin "2") (pinfunction "2_2") (pintype "passive"))
    )
    (net (code "62") (name "Net-(LED7-Pad2)") (class "Default")
      (node (ref "LED7") (pin "2") (pinfunction "2_2") (pintype "passive"))
      (node (ref "R19") (pin "2") (pinfunction "2_2") (pintype "passive"))
    )
    (net (code "63") (name "Net-(LED8-Pad2)") (class "Default")
      (node (ref "LED8") (pin "2") (pinfunction "2_2") (pintype "passive"))
      (node (ref "R20") (pin "2") (pinfunction "2_2") (pintype "passive"))
    )
    (net (code "64") (name "Net-(LED9-Pad2)") (class "Default")
      (node (ref "LED9") (pin "2") (pinfunction "2_2") (pintype "passive"))
      (node (ref "R21") (pin "2") (pinfunction "2_2") (pintype "passive"))
    )
    (net (code "65") (name "Net-(LED10-Pad2)") (class "Default")
      (node (ref "LED10") (pin "2") (pinfunction "2_2") (pintype "passive"))
      (node (ref "R22") (pin "2") (pinfunction "2_2") (pintype "passive"))
    )
    (net (code "66") (name "Net-(LED11-Pad2)") (class "Default")
      (node (ref "LED11") (pin "2") (pinfunction "2_2") (pintype "passive"))
      (node (ref "R23") (pin "2") (pinfunction "2_2") (pintype "passive"))
    )
    (net (code "67") (name "Net-(Q1-PadB)") (class "Default")
      (node (ref "Q1") (pin "B") (pinfunction "B_B") (pintype "passive"))
      (node (ref "R8") (pin "2") (pinfunction "2_2") (pintype "passive"))
    )
    (net (code "68") (name "Net-(Q1-PadE)") (class "Default")
      (node (ref "Q1") (pin "E") (pinfunction "E_E") (pintype "passive"))
      (node (ref "R9") (pin "2") (pinfunction "2_2") (pintype "passive"))
    )
    (net (code "69") (name "Net-(U1-BOOT)") (class "Default")
      (node (ref "C11") (pin "1") (pinfunction "1_1") (pintype "passive"))
      (node (ref "U1") (pin "1") (pinfunction "BOOT_1") (pintype "passive"))
    )
    (net (code "70") (name "Net-(U1-VSNS)") (class "Default")
      (node (ref "R1") (pin "1") (pinfunction "1_1") (pintype "passive"))
      (node (ref "R2") (pin "2") (pinfunction "2_2") (pintype "passive"))
      (node (ref "U1") (pin "4") (pinfunction "VSNS_4") (pintype "passive"))
    )
    (net (code "71") (name "Net-(U3A-IN+)") (class "Default")
      (node (ref "R6") (pin "1") (pinfunction "1_1") (pintype "passive"))
      (node (ref "R7") (pin "2") (pinfunction "2_2") (pintype "passive"))
      (node (ref "U3") (pin "3") (pinfunction "IN+_3") (pintype "input"))
    )
    (net (code "72") (name "Net-(U3A-IN-)") (class "Default")
      (node (ref "P8") (pin "3") (pinfunction "3_3") (pintype "passive"))
      (node (ref "U3") (pin "1") (pinfunction "OUT_1") (pintype "output"))
      (node (ref "U3") (pin "2") (pinfunction "IN-_2") (pintype "input"))
    )
    (net (code "73") (name "Net-(U3A-V+)") (class "Default")
      (node (ref "P8") (pin "1") (pinfunction "1_1") (pintype "passive"))
      (node (ref "U3") (pin "8") (pinfunction "V+_8") (pintype "power_in"))
    )
    (net (code "74") (name "Net-(U4-1A1)") (class "Default")
      (node (ref "U4") (pin "5") (pinfunction "1A1_5") (pintype "input"))
      (node (ref "U6") (pin "3") (pinfunction "~{O}_3") (pintype "output"))
    )
    (net (code "75") (name "Net-(U4-1E)") (class "Default")
      (node (ref "R15") (pin "2") (pinfunction "2_2") (pintype "passive"))
      (node (ref "U4") (pin "1") (pinfunction "1E_1") (pintype "passive"))
    )
    (net (code "76") (name "Net-(U4-2A1)") (class "Default")
      (node (ref "U4") (pin "10") (pinfunction "2A1_10") (pintype "input"))
      (node (ref "U6") (pin "6") (pinfunction "~{O}_6") (pintype "output"))
    )
    (net (code "77") (name "Net-(U4-2E)") (class "Default")
      (node (ref "R10") (pin "2") (pinfunction "2_2") (pintype "passive"))
      (node (ref "U4") (pin "15") (pinfunction "2E_15") (pintype "passive"))
    )
    (net (code "78") (name "Net-(U5-1A1)") (class "Default")
      (node (ref "U5") (pin "5") (pinfunction "1A1_5") (pintype "input"))
      (node (ref "U6") (pin "11") (pinfunction "~{O}_11") (pintype "output"))
    )
    (net (code "79") (name "Net-(U5-1E)") (class "Default")
      (node (ref "R29") (pin "2") (pinfunction "2_2") (pintype "passive"))
      (node (ref "U5") (pin "1") (pinfunction "1E_1") (pintype "passive"))
    )
    (net (code "80") (name "Net-(U5-2A1)") (class "Default")
      (node (ref "U5") (pin "10") (pinfunction "2A1_10") (pintype "input"))
      (node (ref "U6") (pin "8") (pinfunction "~{O}_8") (pintype "output"))
    )
    (net (code "81") (name "Net-(U5-2E)") (class "Default")
      (node (ref "R28") (pin "2") (pinfunction "2_2") (pintype "passive"))
      (node (ref "U5") (pin "15") (pinfunction "2E_15") (pintype "passive"))
    )
    (net (code "82") (name "VCC") (class "Default")
      (node (ref "Buz") (pin "1") (pinfunction "1_1") (pintype "passive"))
      (node (ref "C4") (pin "1") (pinfunction "1_1") (pintype "passive"))
      (node (ref "C5") (pin "2") (pinfunction "2_2") (pintype "passive"))
      (node (ref "C7") (pin "1") (pinfunction "1_1") (pintype "passive"))
      (node (ref "C9") (pin "1") (pinfunction "1_1") (pintype "passive"))
      (node (ref "L1") (pin "2") (pinfunction "2_2") (pintype "passive"))
      (node (ref "LED2") (pin "1") (pinfunction "1_1") (pintype "passive"))
      (node (ref "P2A") (pin "2") (pinfunction "2_2") (pintype "passive"))
      (node (ref "P4") (pin "3") (pinfunction "3_3") (pintype "passive"))
      (node (ref "P4") (pin "4") (pinfunction "4_4") (pintype "passive"))
      (node (ref "R1") (pin "2") (pinfunction "2_2") (pintype "passive"))
      (node (ref "TP2") (pin "0") (pinfunction "0_0") (pintype "passive"))
      (node (ref "U2") (pin "3") (pinfunction "IN_3") (pintype "passive"))
      (node (ref "U4") (pin "9") (pinfunction "VCCL_9") (pintype "power_in"))
      (node (ref "U5") (pin "9") (pinfunction "VCCL_9") (pintype "power_in"))
      (node (ref "U6") (pin "14") (pinfunction "VCC_14") (pintype "power_in"))
    )
    (net (code "83") (name "Vin") (class "Default")
      (node (ref "C10") (pin "2") (pinfunction "2_2") (pintype "passive"))
      (node (ref "C8") (pin "2") (pinfunction "2_2") (pintype "passive"))
      (node (ref "D10") (pin "2") (pinfunction "K_2") (pintype "passive"))
      (node (ref "D11") (pin "2") (pinfunction "K_2") (pintype "passive"))
      (node (ref "D12") (pin "2") (pinfunction "K_2") (pintype "passive"))
      (node (ref "D13") (pin "2") (pinfunction "K_2") (pintype "passive"))
      (node (ref "D2") (pin "2") (pinfunction "K_2") (pintype "passive"))
      (node (ref "D3") (pin "2") (pinfunction "K_2") (pintype "passive"))
      (node (ref "D4") (pin "2") (pinfunction "K_2") (pintype "passive"))
      (node (ref "D5") (pin "2") (pinfunction "K_2") (pintype "passive"))
      (node (ref "F1") (pin "2") (pinfunction "2_2") (pintype "passive"))
      (node (ref "LED1") (pin "1") (pinfunction "1_1") (pintype "passive"))
      (node (ref "PushSWtme1") (pin "1") (pinfunction "1_1") (pintype "passive"))
      (node (ref "PushSWtme1") (pin "4") (pinfunction "4_4") (pintype "passive"))
      (node (ref "R6") (pin "2") (pinfunction "2_2") (pintype "passive"))
      (node (ref "U4") (pin "4") (pinfunction "VCCH_4") (pintype "power_in"))
      (node (ref "U5") (pin "4") (pinfunction "VCCH_4") (pintype "power_in"))
    )
    (net (code "84") (name "unconnected-(H1-Pad0)") (class "Default")
      (node (ref "H1") (pin "0") (pinfunction "0_0") (pintype "passive"))
    )
    (net (code "85") (name "unconnected-(H1-Pad1)") (class "Default")
      (node (ref "H1") (pin "1") (pinfunction "1_1") (pintype "passive"))
    )
    (net (code "86") (name "unconnected-(H2-Pad0)") (class "Default")
      (node (ref "H2") (pin "0") (pinfunction "0_0") (pintype "passive"))
    )
    (net (code "87") (name "unconnected-(H2-Pad1)") (class "Default")
      (node (ref "H2") (pin "1") (pinfunction "1_1") (pintype "passive"))
    )
    (net (code "88") (name "unconnected-(PushSWtme1-Pad3)") (class "Default")
      (node (ref "PushSWtme1") (pin "3") (pinfunction "3_3") (pintype "passive"))
    )
    (net (code "89") (name "unconnected-(PushSWtme1-Pad6)") (class "Default")
      (node (ref "PushSWtme1") (pin "6") (pinfunction "6_6") (pintype "passive"))
    )
    (net (code "90") (name "unconnected-(U1-ENA-Pad5)") (class "Default")
      (node (ref "U1") (pin "5") (pinfunction "ENA_5") (pintype "passive+no_connect"))
    )
    (net (code "91") (name "unconnected-(U1-NC-Pad2)") (class "Default")
      (node (ref "U1") (pin "2") (pinfunction "NC_2") (pintype "passive"))
    )
    (net (code "92") (name "unconnected-(U1-NC-Pad3)") (class "Default")
      (node (ref "U1") (pin "3") (pinfunction "NC_3") (pintype "passive"))
    )
    (net (code "93") (name "unconnected-(U3B-OUT-Pad7)") (class "Default")
      (node (ref "U3") (pin "7") (pinfunction "OUT_7") (pintype "output"))
    )
  )
)
